# main.net
KiCad netlist of a schematic drawn in EAGLE
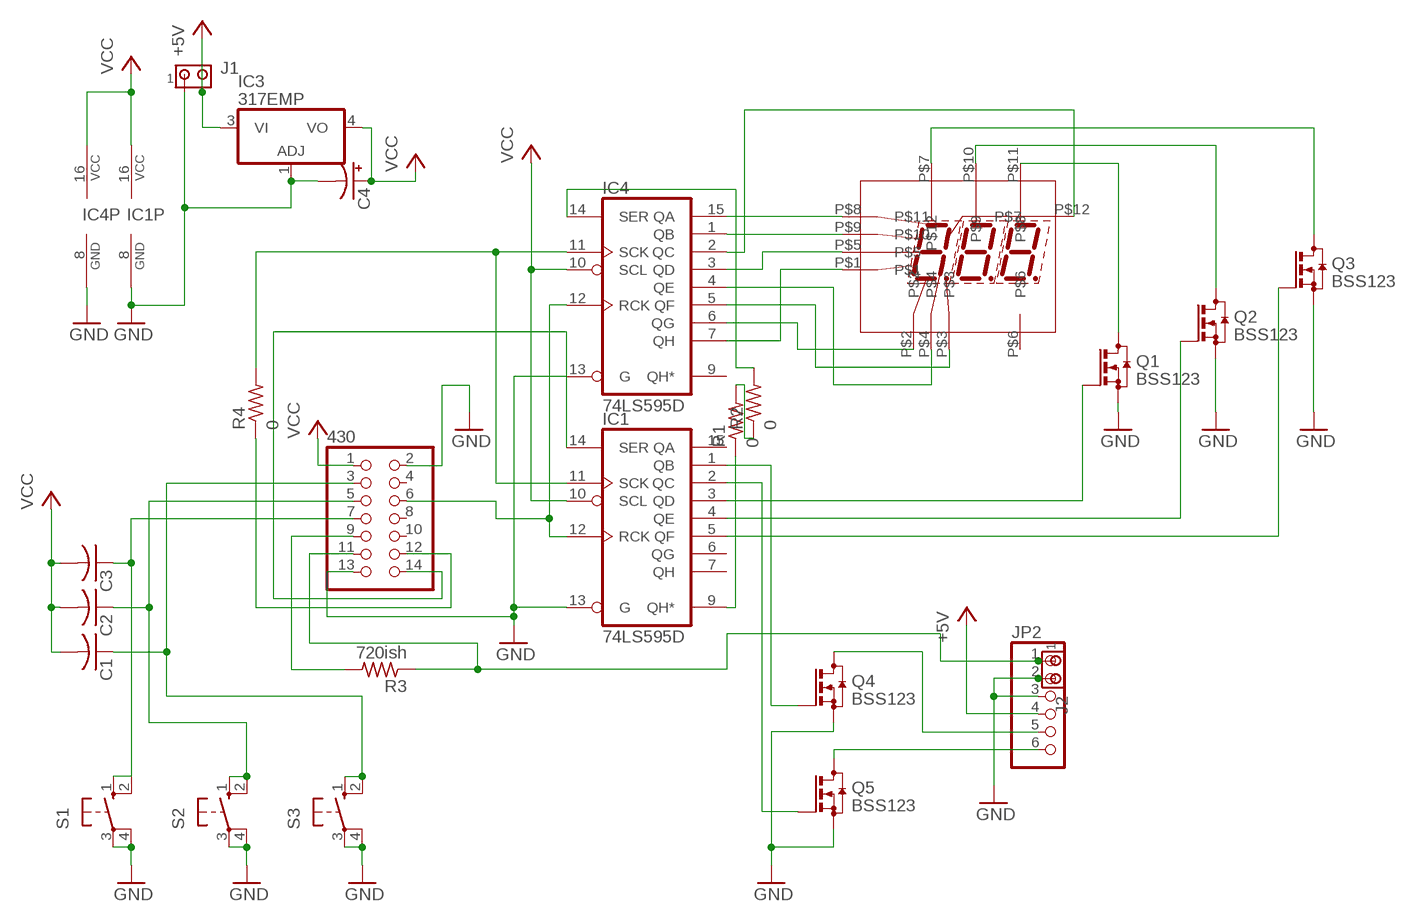
[diagram p0: schematic, sheet 1]

(export (version "E")
  (design (tool "Eeschema 10.0.6"))
  (components
    (comp (ref "430")
      (value "PINHD-2X7")
      (footprint "eagle-import:2X07")
      (libsource (lib "eagle-import") (part "PINHD-2X7"))
    )
    (comp (ref "C1")
      (value "C-USC0603K")
      (footprint "eagle-import:C0603K")
      (libsource (lib "eagle-import") (part "C-USC0603K"))
    )
    (comp (ref "C2")
      (value "C-USC0603K")
      (footprint "eagle-import:C0603K")
      (libsource (lib "eagle-import") (part "C-USC0603K"))
    )
    (comp (ref "C3")
      (value "C-USC0603K")
      (footprint "eagle-import:C0603K")
      (libsource (lib "eagle-import") (part "C-USC0603K"))
    )
    (comp (ref "C4")
      (value "CPOL-USE2.5-7")
      (footprint "eagle-import:E2,5-7")
      (libsource (lib "eagle-import") (part "CPOL-USE2.5-7"))
    )
    (comp (ref "IC1")
      (value "74LS595D")
      (footprint "eagle-import:SO16")
      (libsource (lib "eagle-import") (part "74595DLS"))
    )
    (comp (ref "IC3")
      (value "317EMP")
      (footprint "eagle-import:SOT223")
      (libsource (lib "eagle-import") (part "317EMP"))
    )
    (comp (ref "IC4")
      (value "74LS595D")
      (footprint "eagle-import:SO16")
      (libsource (lib "eagle-import") (part "74595DLS"))
    )
    (comp (ref "J1")
      (value "MTA02-100")
      (footprint "eagle-import:10X02MTA")
      (libsource (lib "eagle-import") (part "MTA02-100"))
    )
    (comp (ref "J2")
      (value "MTA02-100")
      (footprint "eagle-import:10X02MTA")
      (libsource (lib "eagle-import") (part "MTA02-100"))
    )
    (comp (ref "JP2")
      (value "PINHD-1X6")
      (footprint "eagle-import:1X06")
      (libsource (lib "eagle-import") (part "PINHD-1X6"))
    )
    (comp (ref "Q1")
      (value "BSS123")
      (footprint "eagle-import:SOT23")
      (libsource (lib "eagle-import") (part "BSS123"))
    )
    (comp (ref "Q2")
      (value "BSS123")
      (footprint "eagle-import:SOT23")
      (libsource (lib "eagle-import") (part "BSS123"))
    )
    (comp (ref "Q3")
      (value "BSS123")
      (footprint "eagle-import:SOT23")
      (libsource (lib "eagle-import") (part "BSS123"))
    )
    (comp (ref "Q4")
      (value "BSS123")
      (footprint "eagle-import:SOT23")
      (libsource (lib "eagle-import") (part "BSS123"))
    )
    (comp (ref "Q5")
      (value "BSS123")
      (footprint "eagle-import:SOT23")
      (libsource (lib "eagle-import") (part "BSS123"))
    )
    (comp (ref "R1")
      (value "0")
      (footprint "eagle-import:R0603")
      (libsource (lib "eagle-import") (part "R-US_R0603"))
    )
    (comp (ref "R2")
      (value "0")
      (footprint "eagle-import:R0603")
      (libsource (lib "eagle-import") (part "R-US_R0603"))
    )
    (comp (ref "R3")
      (value "720ish")
      (footprint "eagle-import:R0805")
      (libsource (lib "eagle-import") (part "R-US_R0805"))
    )
    (comp (ref "R4")
      (value "0")
      (footprint "eagle-import:R0603")
      (libsource (lib "eagle-import") (part "R-US_R0603"))
    )
    (comp (ref "S1")
      (value "10-XX")
      (footprint "eagle-import:B3F-10XX")
      (fields (field (name "MPN") "B3F-1000"))
      (libsource (lib "eagle-import") (part "10-XX"))
    )
    (comp (ref "S2")
      (value "10-XX")
      (footprint "eagle-import:B3F-10XX")
      (fields (field (name "MPN") "B3F-1000"))
      (libsource (lib "eagle-import") (part "10-XX"))
    )
    (comp (ref "S3")
      (value "10-XX")
      (footprint "eagle-import:B3F-10XX")
      (fields (field (name "MPN") "B3F-1000"))
      (libsource (lib "eagle-import") (part "10-XX"))
    )
    (comp (ref "U$1")
      (value "BL-T52C-31")
      (footprint "eagle-import:BL-T52X-31")
      (libsource (lib "eagle-import") (part "BL-T52C-31"))
    )
  )
  (nets
    (net (code "1") (name "+5V") (class "Default")
      (node (ref "IC3") (pin "3") (pinfunction "VI_3") (pintype "input"))
      (node (ref "J1") (pin "2") (pinfunction "2_2") (pintype "passive"))
      (node (ref "JP2") (pin "4") (pinfunction "4_4") (pintype "passive"))
    )
    (net (code "2") (name "GND") (class "Default")
      (node (ref "430") (pin "13") (pinfunction "13_13") (pintype "passive"))
      (node (ref "430") (pin "2") (pinfunction "2_2") (pintype "passive"))
      (node (ref "C4") (pin "-") (pinfunction "-_-") (pintype "passive"))
      (node (ref "IC1") (pin "13") (pinfunction "G_13") (pintype "input"))
      (node (ref "IC1") (pin "8") (pinfunction "GND_8") (pintype "power_in"))
      (node (ref "IC3") (pin "1") (pinfunction "ADJ_1") (pintype "input"))
      (node (ref "IC4") (pin "13") (pinfunction "G_13") (pintype "input"))
      (node (ref "IC4") (pin "8") (pinfunction "GND_8") (pintype "power_in"))
      (node (ref "J1") (pin "1") (pinfunction "1_1") (pintype "passive"))
      (node (ref "J2") (pin "2") (pinfunction "2_2") (pintype "passive"))
      (node (ref "JP2") (pin "2") (pinfunction "2_2") (pintype "passive"))
      (node (ref "JP2") (pin "3") (pinfunction "3_3") (pintype "passive"))
      (node (ref "Q1") (pin "2") (pinfunction "S_2") (pintype "passive"))
      (node (ref "Q2") (pin "2") (pinfunction "S_2") (pintype "passive"))
      (node (ref "Q3") (pin "2") (pinfunction "S_2") (pintype "passive"))
      (node (ref "Q4") (pin "2") (pinfunction "S_2") (pintype "passive"))
      (node (ref "Q5") (pin "2") (pinfunction "S_2") (pintype "passive"))
      (node (ref "S1") (pin "3") (pinfunction "P_3") (pintype "passive"))
      (node (ref "S1") (pin "4") (pinfunction "P1_4") (pintype "passive"))
      (node (ref "S2") (pin "3") (pinfunction "P_3") (pintype "passive"))
      (node (ref "S2") (pin "4") (pinfunction "P1_4") (pintype "passive"))
      (node (ref "S3") (pin "3") (pinfunction "P_3") (pintype "passive"))
      (node (ref "S3") (pin "4") (pinfunction "P1_4") (pintype "passive"))
    )
    (net (code "3") (name "Net-(430-Pad9)") (class "Default")
      (node (ref "430") (pin "9") (pinfunction "9_9") (pintype "passive"))
      (node (ref "R3") (pin "2") (pinfunction "2_2") (pintype "passive"))
    )
    (net (code "4") (name "Net-(430-Pad11)") (class "Default")
      (node (ref "430") (pin "11") (pinfunction "11_11") (pintype "passive"))
      (node (ref "J2") (pin "1") (pinfunction "1_1") (pintype "passive"))
      (node (ref "JP2") (pin "1") (pinfunction "1_1") (pintype "passive"))
      (node (ref "R3") (pin "1") (pinfunction "1_1") (pintype "passive"))
    )
    (net (code "5") (name "Net-(430-Pad12)") (class "Default")
      (node (ref "430") (pin "12") (pinfunction "12_12") (pintype "passive"))
      (node (ref "R4") (pin "1") (pinfunction "1_1") (pintype "passive"))
    )
    (net (code "6") (name "Net-(IC1A-QB)") (class "Default")
      (node (ref "IC1") (pin "1") (pinfunction "QB_1") (pintype "tri_state"))
      (node (ref "Q4") (pin "1") (pinfunction "G_1") (pintype "passive"))
    )
    (net (code "7") (name "Net-(IC1A-QC)") (class "Default")
      (node (ref "IC1") (pin "2") (pinfunction "QC_2") (pintype "tri_state"))
      (node (ref "Q5") (pin "1") (pinfunction "G_1") (pintype "passive"))
    )
    (net (code "8") (name "Net-(IC1A-QD)") (class "Default")
      (node (ref "IC1") (pin "3") (pinfunction "QD_3") (pintype "tri_state"))
      (node (ref "Q1") (pin "1") (pinfunction "G_1") (pintype "passive"))
    )
    (net (code "9") (name "Net-(IC1A-QE)") (class "Default")
      (node (ref "IC1") (pin "4") (pinfunction "QE_4") (pintype "tri_state"))
      (node (ref "Q2") (pin "1") (pinfunction "G_1") (pintype "passive"))
    )
    (net (code "10") (name "Net-(IC1A-QF)") (class "Default")
      (node (ref "IC1") (pin "5") (pinfunction "QF_5") (pintype "tri_state"))
      (node (ref "Q3") (pin "1") (pinfunction "G_1") (pintype "passive"))
    )
    (net (code "11") (name "Net-(IC1A-QH*)") (class "Default")
      (node (ref "IC1") (pin "9") (pinfunction "QH*_9") (pintype "tri_state"))
      (node (ref "R1") (pin "1") (pinfunction "1_1") (pintype "passive"))
    )
    (net (code "12") (name "Net-(IC1A-RCK)") (class "Default")
      (node (ref "430") (pin "6") (pinfunction "6_6") (pintype "passive"))
      (node (ref "IC1") (pin "12") (pinfunction "RCK_12") (pintype "input"))
      (node (ref "IC4") (pin "12") (pinfunction "RCK_12") (pintype "input"))
    )
    (net (code "13") (name "Net-(IC1A-SCK)") (class "Default")
      (node (ref "IC1") (pin "11") (pinfunction "SCK_11") (pintype "input"))
      (node (ref "IC4") (pin "11") (pinfunction "SCK_11") (pintype "input"))
      (node (ref "R4") (pin "2") (pinfunction "2_2") (pintype "passive"))
    )
    (net (code "14") (name "Net-(IC1A-SER)") (class "Default")
      (node (ref "430") (pin "14") (pinfunction "14_14") (pintype "passive"))
      (node (ref "IC1") (pin "14") (pinfunction "SER_14") (pintype "input"))
    )
    (net (code "15") (name "Net-(IC4A-QA)") (class "Default")
      (node (ref "IC4") (pin "15") (pinfunction "QA_15") (pintype "tri_state"))
      (node (ref "U$1") (pin "P$8") (pinfunction "P$11_P$8") (pintype "bidirectional"))
    )
    (net (code "16") (name "Net-(IC4A-QB)") (class "Default")
      (node (ref "IC4") (pin "1") (pinfunction "QB_1") (pintype "tri_state"))
      (node (ref "U$1") (pin "P$9") (pinfunction "P$10_P$9") (pintype "bidirectional"))
    )
    (net (code "17") (name "Net-(IC4A-QC)") (class "Default")
      (node (ref "IC4") (pin "2") (pinfunction "QC_2") (pintype "tri_state"))
      (node (ref "U$1") (pin "P$12") (pinfunction "P$7_P$12") (pintype "bidirectional"))
    )
    (net (code "18") (name "Net-(IC4A-QD)") (class "Default")
      (node (ref "IC4") (pin "3") (pinfunction "QD_3") (pintype "tri_state"))
      (node (ref "U$1") (pin "P$5") (pinfunction "P$5_P$5") (pintype "bidirectional"))
    )
    (net (code "19") (name "Net-(IC4A-QE)") (class "Default")
      (node (ref "IC4") (pin "4") (pinfunction "QE_4") (pintype "tri_state"))
      (node (ref "U$1") (pin "P$4") (pinfunction "P$4_P$4") (pintype "bidirectional"))
    )
    (net (code "20") (name "Net-(IC4A-QF)") (class "Default")
      (node (ref "IC4") (pin "5") (pinfunction "QF_5") (pintype "tri_state"))
      (node (ref "U$1") (pin "P$3") (pinfunction "P$3_P$3") (pintype "bidirectional"))
    )
    (net (code "21") (name "Net-(IC4A-QG)") (class "Default")
      (node (ref "IC4") (pin "6") (pinfunction "QG_6") (pintype "tri_state"))
      (node (ref "U$1") (pin "P$2") (pinfunction "P$2_P$2") (pintype "bidirectional"))
    )
    (net (code "22") (name "Net-(IC4A-QH)") (class "Default")
      (node (ref "IC4") (pin "7") (pinfunction "QH_7") (pintype "tri_state"))
      (node (ref "U$1") (pin "P$1") (pinfunction "P$1_P$1") (pintype "bidirectional"))
    )
    (net (code "23") (name "Net-(IC4A-SER)") (class "Default")
      (node (ref "IC4") (pin "14") (pinfunction "SER_14") (pintype "input"))
      (node (ref "R2") (pin "2") (pinfunction "2_2") (pintype "passive"))
    )
    (net (code "24") (name "Net-(Q1-D)") (class "Default")
      (node (ref "Q1") (pin "3") (pinfunction "D_3") (pintype "passive"))
      (node (ref "U$1") (pin "P$11") (pinfunction "P$8_P$11") (pintype "bidirectional"))
    )
    (net (code "25") (name "Net-(Q2-D)") (class "Default")
      (node (ref "Q2") (pin "3") (pinfunction "D_3") (pintype "passive"))
      (node (ref "U$1") (pin "P$10") (pinfunction "P$9_P$10") (pintype "bidirectional"))
    )
    (net (code "26") (name "Net-(Q3-D)") (class "Default")
      (node (ref "Q3") (pin "3") (pinfunction "D_3") (pintype "passive"))
      (node (ref "U$1") (pin "P$7") (pinfunction "P$12_P$7") (pintype "bidirectional"))
    )
    (net (code "27") (name "Net-(Q4-D)") (class "Default")
      (node (ref "JP2") (pin "5") (pinfunction "5_5") (pintype "passive"))
      (node (ref "Q4") (pin "3") (pinfunction "D_3") (pintype "passive"))
    )
    (net (code "28") (name "Net-(Q5-D)") (class "Default")
      (node (ref "JP2") (pin "6") (pinfunction "6_6") (pintype "passive"))
      (node (ref "Q5") (pin "3") (pinfunction "D_3") (pintype "passive"))
    )
    (net (code "29") (name "Net-(R1-Pad2)") (class "Default")
      (node (ref "R1") (pin "2") (pinfunction "2_2") (pintype "passive"))
      (node (ref "R2") (pin "1") (pinfunction "1_1") (pintype "passive"))
    )
    (net (code "30") (name "Net-(S1-S)") (class "Default")
      (node (ref "430") (pin "7") (pinfunction "7_7") (pintype "passive"))
      (node (ref "C3") (pin "1") (pinfunction "1_1") (pintype "passive"))
      (node (ref "S1") (pin "1") (pinfunction "S_1") (pintype "passive"))
      (node (ref "S1") (pin "2") (pinfunction "S1_2") (pintype "passive"))
    )
    (net (code "31") (name "Net-(S2-S)") (class "Default")
      (node (ref "430") (pin "5") (pinfunction "5_5") (pintype "passive"))
      (node (ref "C2") (pin "1") (pinfunction "1_1") (pintype "passive"))
      (node (ref "S2") (pin "1") (pinfunction "S_1") (pintype "passive"))
      (node (ref "S2") (pin "2") (pinfunction "S1_2") (pintype "passive"))
    )
    (net (code "32") (name "Net-(S3-S)") (class "Default")
      (node (ref "430") (pin "3") (pinfunction "3_3") (pintype "passive"))
      (node (ref "C1") (pin "1") (pinfunction "1_1") (pintype "passive"))
      (node (ref "S3") (pin "1") (pinfunction "S_1") (pintype "passive"))
      (node (ref "S3") (pin "2") (pinfunction "S1_2") (pintype "passive"))
    )
    (net (code "33") (name "VCC") (class "Default")
      (node (ref "430") (pin "1") (pinfunction "1_1") (pintype "passive"))
      (node (ref "C1") (pin "2") (pinfunction "2_2") (pintype "passive"))
      (node (ref "C2") (pin "2") (pinfunction "2_2") (pintype "passive"))
      (node (ref "C3") (pin "2") (pinfunction "2_2") (pintype "passive"))
      (node (ref "C4") (pin "+") (pinfunction "+_+") (pintype "passive"))
      (node (ref "IC1") (pin "10") (pinfunction "SCL_10") (pintype "input"))
      (node (ref "IC1") (pin "16") (pinfunction "VCC_16") (pintype "power_in"))
      (node (ref "IC3") (pin "4") (pinfunction "VO_4") (pintype "passive"))
      (node (ref "IC4") (pin "10") (pinfunction "SCL_10") (pintype "input"))
      (node (ref "IC4") (pin "16") (pinfunction "VCC_16") (pintype "power_in"))
    )
    (net (code "34") (name "unconnected-(430-Pad4)") (class "Default")
      (node (ref "430") (pin "4") (pinfunction "4_4") (pintype "passive"))
    )
    (net (code "35") (name "unconnected-(430-Pad8)") (class "Default")
      (node (ref "430") (pin "8") (pinfunction "8_8") (pintype "passive"))
    )
    (net (code "36") (name "unconnected-(430-Pad10)") (class "Default")
      (node (ref "430") (pin "10") (pinfunction "10_10") (pintype "passive"))
    )
    (net (code "37") (name "unconnected-(IC1A-QA-Pad15)") (class "Default")
      (node (ref "IC1") (pin "15") (pinfunction "QA_15") (pintype "tri_state"))
    )
    (net (code "38") (name "unconnected-(IC1A-QG-Pad6)") (class "Default")
      (node (ref "IC1") (pin "6") (pinfunction "QG_6") (pintype "tri_state"))
    )
    (net (code "39") (name "unconnected-(IC1A-QH-Pad7)") (class "Default")
      (node (ref "IC1") (pin "7") (pinfunction "QH_7") (pintype "tri_state"))
    )
    (net (code "40") (name "unconnected-(IC4A-QH*-Pad9)") (class "Default")
      (node (ref "IC4") (pin "9") (pinfunction "QH*_9") (pintype "tri_state"))
    )
    (net (code "41") (name "unconnected-(U$1-PadP$6)") (class "Default")
      (node (ref "U$1") (pin "P$6") (pinfunction "P$6_P$6") (pintype "bidirectional"))
    )
  )
)
